# march_23_20_power_board1_v2_0.net
KiCad netlist of a schematic drawn in EAGLE
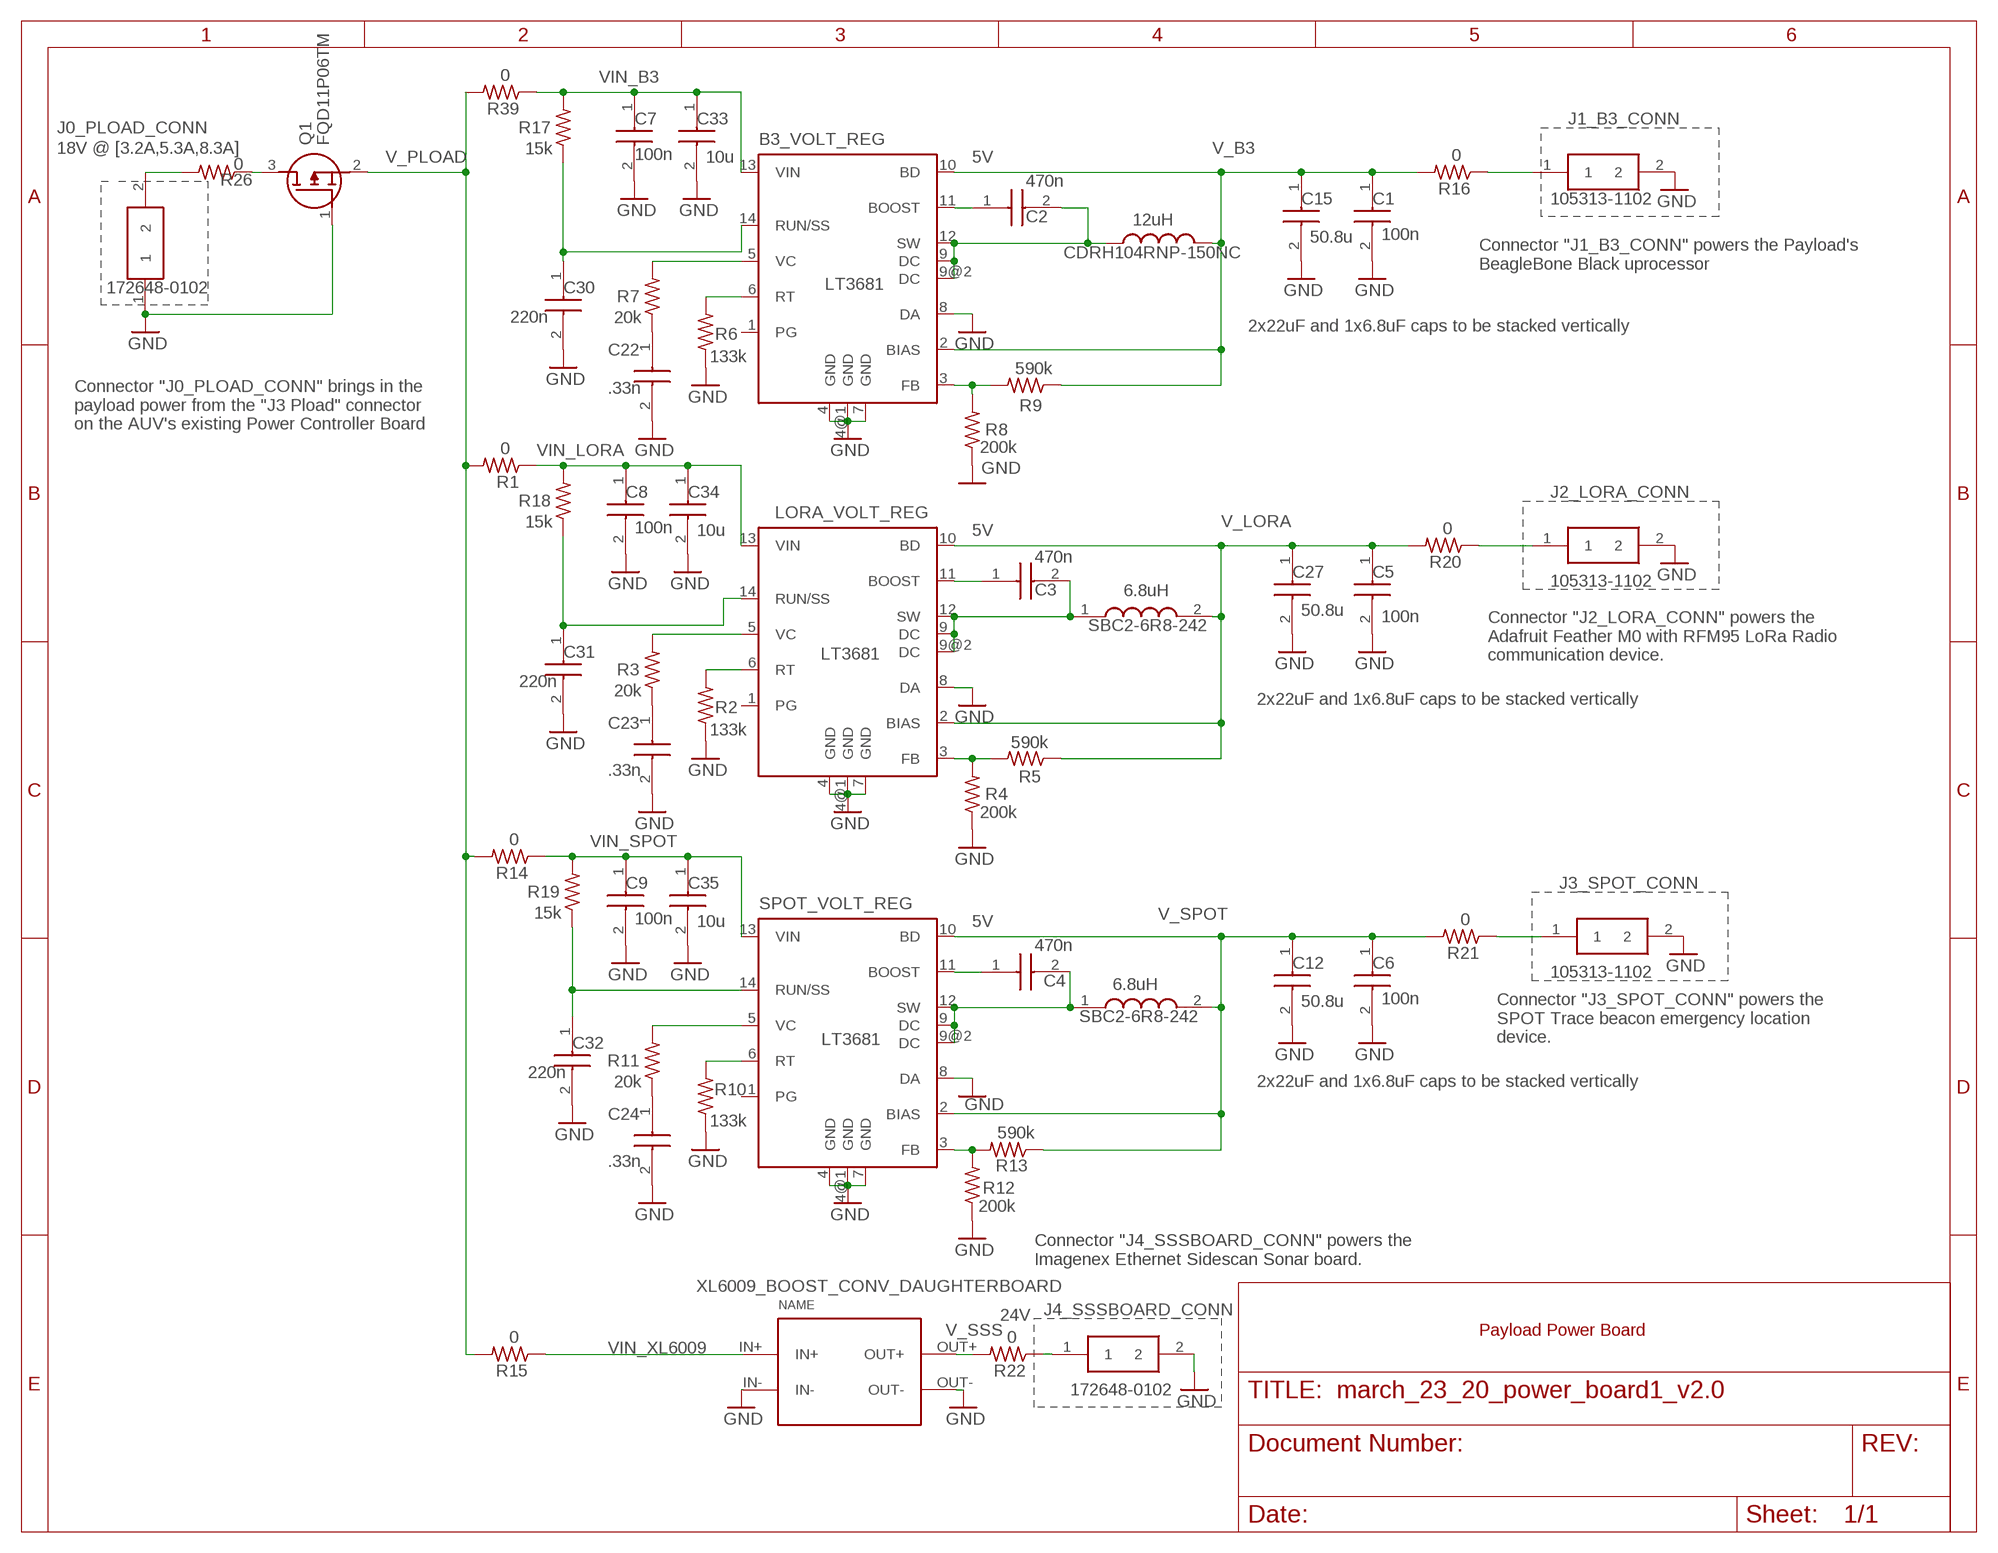
[diagram p0: schematic, sheet 1]

(export (version "E")
  (design (tool "Eeschema 10.0.6"))
  (components
    (comp (ref "B3_VOLT_REG")
      (value "LT3681")
      (footprint "eagle-import:DFN14-4X3DE")
      (fields (field (name "MPN") "LT3681EDE#PBF"))
      (libsource (lib "eagle-import") (part "LT3681"))
    )
    (comp (ref "C1")
      (value "100n")
      (footprint "eagle-import:CAPC1608X90N")
      (fields
        (field (name "MANUFACTURER_PART_NUMBER") "06033C104KAT4A")
        (field (name "MOUSER_PART_NUMBER") "581-06033C104KAT4A")
      )
      (libsource (lib "eagle-import") (part "06033C104KAT4A"))
    )
    (comp (ref "C2")
      (value "470n")
      (footprint "eagle-import:CAPC1608X90N")
      (fields
        (field (name "MANUFACTURER_PART_NUMBER") "06033C474JAT2A")
        (field (name "MOUSER_PART_NUMBER") "581-06033C474JAT2A")
      )
      (libsource (lib "eagle-import") (part "06033C474JAT2A"))
    )
    (comp (ref "C3")
      (value "470n")
      (footprint "eagle-import:CAPC1608X90N")
      (fields
        (field (name "MANUFACTURER_PART_NUMBER") "06033C474JAT2A")
        (field (name "MOUSER_PART_NUMBER") "581-06033C474JAT2A")
      )
      (libsource (lib "eagle-import") (part "06033C474JAT2A"))
    )
    (comp (ref "C4")
      (value "470n")
      (footprint "eagle-import:CAPC1608X90N")
      (fields
        (field (name "MANUFACTURER_PART_NUMBER") "06033C474JAT2A")
        (field (name "MOUSER_PART_NUMBER") "581-06033C474JAT2A")
      )
      (libsource (lib "eagle-import") (part "06033C474JAT2A"))
    )
    (comp (ref "C5")
      (value "100n")
      (footprint "eagle-import:CAPC1608X90N")
      (fields
        (field (name "MANUFACTURER_PART_NUMBER") "06033C104KAT4A")
        (field (name "MOUSER_PART_NUMBER") "581-06033C104KAT4A")
      )
      (libsource (lib "eagle-import") (part "06033C104KAT4A"))
    )
    (comp (ref "C6")
      (value "100n")
      (footprint "eagle-import:CAPC1608X90N")
      (fields
        (field (name "MANUFACTURER_PART_NUMBER") "06033C104KAT4A")
        (field (name "MOUSER_PART_NUMBER") "581-06033C104KAT4A")
      )
      (libsource (lib "eagle-import") (part "06033C104KAT4A"))
    )
    (comp (ref "C7")
      (value "100n")
      (footprint "eagle-import:CAPC1608X90N")
      (fields
        (field (name "MANUFACTURER_PART_NUMBER") "06031C104KAT2A")
        (field (name "MOUSER_PART_NUMBER") "581-06031C104KAT2A")
      )
      (libsource (lib "eagle-import") (part "06031C104KAT2A"))
    )
    (comp (ref "C8")
      (value "100n")
      (footprint "eagle-import:CAPC1608X90N")
      (fields
        (field (name "MANUFACTURER_PART_NUMBER") "06031C104KAT2A")
        (field (name "MOUSER_PART_NUMBER") "581-06031C104KAT2A")
      )
      (libsource (lib "eagle-import") (part "06031C104KAT2A"))
    )
    (comp (ref "C9")
      (value "100n")
      (footprint "eagle-import:CAPC1608X90N")
      (fields
        (field (name "MANUFACTURER_PART_NUMBER") "06031C104KAT2A")
        (field (name "MOUSER_PART_NUMBER") "581-06031C104KAT2A")
      )
      (libsource (lib "eagle-import") (part "06031C104KAT2A"))
    )
    (comp (ref "C12")
      (value "50.8u")
      (footprint "eagle-import:CAPC3225X279N")
      (fields
        (field (name "MANUFACTURER_PART_NUMBER") "12103C226KAT2A")
        (field (name "MOUSER_PART_NUMBER") "581-12103C226KAT2A")
      )
      (libsource (lib "eagle-import") (part "12103C226KAT2A"))
    )
    (comp (ref "C15")
      (value "50.8u")
      (footprint "eagle-import:CAPC3225X279N")
      (fields
        (field (name "MANUFACTURER_PART_NUMBER") "12103C226KAT2A")
        (field (name "MOUSER_PART_NUMBER") "581-12103C226KAT2A")
      )
      (libsource (lib "eagle-import") (part "12103C226KAT2A"))
    )
    (comp (ref "C22")
      (value ".33n")
      (footprint "eagle-import:CAPC2012X140N")
      (fields
        (field (name "MANUFACTURER_PART_NUMBER") "08053C334KAT2A")
        (field (name "MOUSER_PART_NUMBER") "581-08053C334KAT2A")
        (field (name "RS_PART_NUMBER") "1747387")
      )
      (libsource (lib "eagle-import") (part "08053C334KAT2A"))
    )
    (comp (ref "C23")
      (value ".33n")
      (footprint "eagle-import:CAPC2012X140N")
      (fields
        (field (name "MANUFACTURER_PART_NUMBER") "08053C334KAT2A")
        (field (name "MOUSER_PART_NUMBER") "581-08053C334KAT2A")
        (field (name "RS_PART_NUMBER") "1747387")
      )
      (libsource (lib "eagle-import") (part "08053C334KAT2A"))
    )
    (comp (ref "C24")
      (value ".33n")
      (footprint "eagle-import:CAPC2012X140N")
      (fields
        (field (name "MANUFACTURER_PART_NUMBER") "08053C334KAT2A")
        (field (name "MOUSER_PART_NUMBER") "581-08053C334KAT2A")
        (field (name "RS_PART_NUMBER") "1747387")
      )
      (libsource (lib "eagle-import") (part "08053C334KAT2A"))
    )
    (comp (ref "C27")
      (value "50.8u")
      (footprint "eagle-import:CAPC3225X279N")
      (fields
        (field (name "MANUFACTURER_PART_NUMBER") "12103C226KAT2A")
        (field (name "MOUSER_PART_NUMBER") "581-12103C226KAT2A")
      )
      (libsource (lib "eagle-import") (part "12103C226KAT2A"))
    )
    (comp (ref "C30")
      (value "220n")
      (footprint "eagle-import:CAPC2012X140N")
      (fields
        (field (name "MANUFACTURER_PART_NUMBER") "08051C224KAT2A")
        (field (name "MOUSER_PART_NUMBER") "581-08051C224KAT2A")
      )
      (libsource (lib "eagle-import") (part "08051C224KAT2A"))
    )
    (comp (ref "C31")
      (value "220n")
      (footprint "eagle-import:CAPC2012X140N")
      (fields
        (field (name "MANUFACTURER_PART_NUMBER") "08051C224KAT2A")
        (field (name "MOUSER_PART_NUMBER") "581-08051C224KAT2A")
      )
      (libsource (lib "eagle-import") (part "08051C224KAT2A"))
    )
    (comp (ref "C32")
      (value "220n")
      (footprint "eagle-import:CAPC2012X140N")
      (fields
        (field (name "MANUFACTURER_PART_NUMBER") "08051C224KAT2A")
        (field (name "MOUSER_PART_NUMBER") "581-08051C224KAT2A")
      )
      (libsource (lib "eagle-import") (part "08051C224KAT2A"))
    )
    (comp (ref "C33")
      (value "10u")
      (footprint "eagle-import:CAPC5750X279N")
      (fields
        (field (name "MANUFACTURER_PART_NUMBER") "22201C106KAT2A")
        (field (name "MOUSER_PART_NUMBER") "581-22201C106KAT2A")
      )
      (libsource (lib "eagle-import") (part "22201C106KAT2A"))
    )
    (comp (ref "C34")
      (value "10u")
      (footprint "eagle-import:CAPC5750X279N")
      (fields
        (field (name "MANUFACTURER_PART_NUMBER") "22201C106KAT2A")
        (field (name "MOUSER_PART_NUMBER") "581-22201C106KAT2A")
      )
      (libsource (lib "eagle-import") (part "22201C106KAT2A"))
    )
    (comp (ref "C35")
      (value "10u")
      (footprint "eagle-import:CAPC5750X279N")
      (fields
        (field (name "MANUFACTURER_PART_NUMBER") "22201C106KAT2A")
        (field (name "MOUSER_PART_NUMBER") "581-22201C106KAT2A")
      )
      (libsource (lib "eagle-import") (part "22201C106KAT2A"))
    )
    (comp (ref "INDUCTOR_3")
      (value "CDRH104RNP-150NC")
      (footprint "eagle-import:INDPM102100X400N")
      (fields (field (name "MOUSER_PART_NUMBER") "851-CDRH104RNP-150NC"))
      (libsource (lib "eagle-import") (part "CDRH104RNP-150NC"))
    )
    (comp (ref "J0_PLOAD_CONN")
      (value "172648-0102")
      (footprint "eagle-import:1726480102")
      (fields (field (name "MOUSER_PART_NUMBER") "538-172648-0102"))
      (libsource (lib "eagle-import") (part "172648-0102"))
    )
    (comp (ref "J1_B3_CONN")
      (value "105313-1102")
      (footprint "eagle-import:1053131102")
      (fields (field (name "MOUSER_PART_NUMBER") "538-105313-1102") (field (name "RS_PART_NUMBER") "1623686"))
      (libsource (lib "eagle-import") (part "105313-1102"))
    )
    (comp (ref "J2_LORA_CONN")
      (value "105313-1102")
      (footprint "eagle-import:1053131102")
      (fields (field (name "MOUSER_PART_NUMBER") "538-105313-1102") (field (name "RS_PART_NUMBER") "1623686"))
      (libsource (lib "eagle-import") (part "105313-1102"))
    )
    (comp (ref "J3_SPOT_CONN")
      (value "105313-1102")
      (footprint "eagle-import:1053131102")
      (fields (field (name "MOUSER_PART_NUMBER") "538-105313-1102") (field (name "RS_PART_NUMBER") "1623686"))
      (libsource (lib "eagle-import") (part "105313-1102"))
    )
    (comp (ref "J4_SSSBOARD_CONN")
      (value "172648-0102")
      (footprint "eagle-import:1726480102")
      (fields (field (name "MOUSER_PART_NUMBER") "538-172648-0102"))
      (libsource (lib "eagle-import") (part "172648-0102"))
    )
    (comp (ref "L4")
      (value "SBC2-6R8-242")
      (footprint "eagle-import:SBC26R8242")
      (fields (field (name "MOUSER_PART_NUMBER") "80-SBC2-6R8-242"))
      (libsource (lib "eagle-import") (part "SBC2-6R8-242"))
    )
    (comp (ref "L5")
      (value "SBC2-6R8-242")
      (footprint "eagle-import:SBC26R8242")
      (fields (field (name "MOUSER_PART_NUMBER") "80-SBC2-6R8-242"))
      (libsource (lib "eagle-import") (part "SBC2-6R8-242"))
    )
    (comp (ref "LORA_VOLT_REG")
      (value "LT3681")
      (footprint "eagle-import:DFN14-4X3DE")
      (fields (field (name "MPN") "LT3681EDE#PBF"))
      (libsource (lib "eagle-import") (part "LT3681"))
    )
    (comp (ref "Q1")
      (value "FQD11P06TM")
      (footprint "eagle-import:DPAK3-CASE-369AS")
      (fields (field (name "MOUSER_PART_NUMBER") "512-FQD11P06TM") (field (name "RS_PART_NUMBER") "6710949P"))
      (libsource (lib "eagle-import") (part "FQD11P06TM"))
    )
    (comp (ref "R1")
      (value "0")
      (footprint "eagle-import:0207_2V")
      (fields (field (name "MFR") "Yageo") (field (name "MPN") "RC0805FR-0710KL"))
      (libsource (lib "eagle-import") (part "R-US_0207/2V"))
    )
    (comp (ref "R2")
      (value "133k")
      (footprint "eagle-import:R0603")
      (libsource (lib "eagle-import") (part "R-US_R0603"))
    )
    (comp (ref "R3")
      (value "20k")
      (footprint "eagle-import:R0603")
      (libsource (lib "eagle-import") (part "R-US_R0603"))
    )
    (comp (ref "R4")
      (value "200k")
      (footprint "eagle-import:R0603")
      (libsource (lib "eagle-import") (part "R-US_R0603"))
    )
    (comp (ref "R5")
      (value "590k")
      (footprint "eagle-import:R0603")
      (libsource (lib "eagle-import") (part "R-US_R0603"))
    )
    (comp (ref "R6")
      (value "133k")
      (footprint "eagle-import:R0603")
      (libsource (lib "eagle-import") (part "R-US_R0603"))
    )
    (comp (ref "R7")
      (value "20k")
      (footprint "eagle-import:R0603")
      (libsource (lib "eagle-import") (part "R-US_R0603"))
    )
    (comp (ref "R8")
      (value "200k")
      (footprint "eagle-import:R0603")
      (libsource (lib "eagle-import") (part "R-US_R0603"))
    )
    (comp (ref "R9")
      (value "590k")
      (footprint "eagle-import:R0603")
      (libsource (lib "eagle-import") (part "R-US_R0603"))
    )
    (comp (ref "R10")
      (value "133k")
      (footprint "eagle-import:R0603")
      (libsource (lib "eagle-import") (part "R-US_R0603"))
    )
    (comp (ref "R11")
      (value "20k")
      (footprint "eagle-import:R0603")
      (libsource (lib "eagle-import") (part "R-US_R0603"))
    )
    (comp (ref "R12")
      (value "200k")
      (footprint "eagle-import:R0603")
      (libsource (lib "eagle-import") (part "R-US_R0603"))
    )
    (comp (ref "R13")
      (value "590k")
      (footprint "eagle-import:R0603")
      (libsource (lib "eagle-import") (part "R-US_R0603"))
    )
    (comp (ref "R14")
      (value "0")
      (footprint "eagle-import:0207_2V")
      (fields (field (name "MFR") "Yageo") (field (name "MPN") "RC0805FR-0710KL"))
      (libsource (lib "eagle-import") (part "R-US_0207/2V"))
    )
    (comp (ref "R15")
      (value "0")
      (footprint "eagle-import:0207_2V")
      (fields (field (name "MFR") "Yageo") (field (name "MPN") "RC0805FR-0710KL"))
      (libsource (lib "eagle-import") (part "R-US_0207/2V"))
    )
    (comp (ref "R16")
      (value "0")
      (footprint "eagle-import:0207_2V")
      (fields (field (name "MFR") "Yageo") (field (name "MPN") "RC0805FR-0710KL"))
      (libsource (lib "eagle-import") (part "R-US_0207/2V"))
    )
    (comp (ref "R17")
      (value "15k")
      (footprint "eagle-import:R0603")
      (libsource (lib "eagle-import") (part "R-US_R0603"))
    )
    (comp (ref "R18")
      (value "15k")
      (footprint "eagle-import:R0603")
      (libsource (lib "eagle-import") (part "R-US_R0603"))
    )
    (comp (ref "R19")
      (value "15k")
      (footprint "eagle-import:R0603")
      (libsource (lib "eagle-import") (part "R-US_R0603"))
    )
    (comp (ref "R20")
      (value "0")
      (footprint "eagle-import:0207_2V")
      (fields (field (name "MFR") "Yageo") (field (name "MPN") "RC0805FR-0710KL"))
      (libsource (lib "eagle-import") (part "R-US_0207/2V"))
    )
    (comp (ref "R21")
      (value "0")
      (footprint "eagle-import:0207_2V")
      (fields (field (name "MFR") "Yageo") (field (name "MPN") "RC0805FR-0710KL"))
      (libsource (lib "eagle-import") (part "R-US_0207/2V"))
    )
    (comp (ref "R22")
      (value "0")
      (footprint "eagle-import:0207_2V")
      (fields (field (name "MFR") "Yageo") (field (name "MPN") "RC0805FR-0710KL"))
      (libsource (lib "eagle-import") (part "R-US_0207/2V"))
    )
    (comp (ref "R26")
      (value "0")
      (footprint "eagle-import:0207_2V")
      (fields (field (name "MFR") "Yageo") (field (name "MPN") "RC0805FR-0710KL"))
      (libsource (lib "eagle-import") (part "R-US_0207/2V"))
    )
    (comp (ref "R39")
      (value "0")
      (footprint "eagle-import:0207_2V")
      (fields (field (name "MFR") "Yageo") (field (name "MPN") "RC0805FR-0710KL"))
      (libsource (lib "eagle-import") (part "R-US_0207/2V"))
    )
    (comp (ref "SPOT_VOLT_REG")
      (value "LT3681")
      (footprint "eagle-import:DFN14-4X3DE")
      (fields (field (name "MPN") "LT3681EDE#PBF"))
      (libsource (lib "eagle-import") (part "LT3681"))
    )
    (comp (ref "XL6009_BOOST_CONV_DAUGHTERBOARD")
      (value "CP8-ADJ")
      (footprint "eagle-import:CP8-ADJ")
      (libsource (lib "eagle-import") (part "CP8-ADJ"))
    )
  )
  (nets
    (net (code "1") (name "/VIN_B3") (class "Default")
      (node (ref "B3_VOLT_REG") (pin "13") (pinfunction "VIN_13") (pintype "input"))
      (node (ref "C33") (pin "1") (pinfunction "1_1") (pintype "bidirectional"))
      (node (ref "C7") (pin "1") (pinfunction "1_1") (pintype "bidirectional"))
      (node (ref "R17") (pin "2") (pinfunction "2_2") (pintype "passive"))
      (node (ref "R39") (pin "1") (pinfunction "1_1") (pintype "passive"))
    )
    (net (code "2") (name "/VIN_LORA") (class "Default")
      (node (ref "C34") (pin "1") (pinfunction "1_1") (pintype "bidirectional"))
      (node (ref "C8") (pin "1") (pinfunction "1_1") (pintype "bidirectional"))
      (node (ref "LORA_VOLT_REG") (pin "13") (pinfunction "VIN_13") (pintype "input"))
      (node (ref "R1") (pin "1") (pinfunction "1_1") (pintype "passive"))
      (node (ref "R18") (pin "2") (pinfunction "2_2") (pintype "passive"))
    )
    (net (code "3") (name "/VIN_SPOT") (class "Default")
      (node (ref "C35") (pin "1") (pinfunction "1_1") (pintype "bidirectional"))
      (node (ref "C9") (pin "1") (pinfunction "1_1") (pintype "bidirectional"))
      (node (ref "R14") (pin "1") (pinfunction "1_1") (pintype "passive"))
      (node (ref "R19") (pin "2") (pinfunction "2_2") (pintype "passive"))
      (node (ref "SPOT_VOLT_REG") (pin "13") (pinfunction "VIN_13") (pintype "input"))
    )
    (net (code "4") (name "/VIN_XL6009") (class "Default")
      (node (ref "R15") (pin "1") (pinfunction "1_1") (pintype "passive"))
      (node (ref "XL6009_BOOST_CONV_DAUGHTERBOARD") (pin "IN+") (pinfunction "IN+_IN+") (pintype "passive"))
    )
    (net (code "5") (name "/V_B3") (class "Default")
      (node (ref "B3_VOLT_REG") (pin "10") (pinfunction "BD_10") (pintype "input"))
      (node (ref "B3_VOLT_REG") (pin "2") (pinfunction "BIAS_2") (pintype "input"))
      (node (ref "C1") (pin "1") (pinfunction "1_1") (pintype "bidirectional"))
      (node (ref "C15") (pin "1") (pinfunction "1_1") (pintype "bidirectional"))
      (node (ref "INDUCTOR_3") (pin "2") (pinfunction "2_2") (pintype "passive"))
      (node (ref "R16") (pin "2") (pinfunction "2_2") (pintype "passive"))
      (node (ref "R9") (pin "1") (pinfunction "1_1") (pintype "passive"))
    )
    (net (code "6") (name "/V_LORA") (class "Default")
      (node (ref "C27") (pin "1") (pinfunction "1_1") (pintype "bidirectional"))
      (node (ref "C5") (pin "1") (pinfunction "1_1") (pintype "bidirectional"))
      (node (ref "L5") (pin "2") (pinfunction "2_2") (pintype "bidirectional"))
      (node (ref "LORA_VOLT_REG") (pin "10") (pinfunction "BD_10") (pintype "input"))
      (node (ref "LORA_VOLT_REG") (pin "2") (pinfunction "BIAS_2") (pintype "input"))
      (node (ref "R20") (pin "2") (pinfunction "2_2") (pintype "passive"))
      (node (ref "R5") (pin "1") (pinfunction "1_1") (pintype "passive"))
    )
    (net (code "7") (name "/V_PLOAD") (class "Default")
      (node (ref "Q1") (pin "2") (pinfunction "S_2") (pintype "bidirectional"))
      (node (ref "R1") (pin "2") (pinfunction "2_2") (pintype "passive"))
      (node (ref "R14") (pin "2") (pinfunction "2_2") (pintype "passive"))
      (node (ref "R15") (pin "2") (pinfunction "2_2") (pintype "passive"))
      (node (ref "R39") (pin "2") (pinfunction "2_2") (pintype "passive"))
    )
    (net (code "8") (name "/V_SPOT") (class "Default")
      (node (ref "C12") (pin "1") (pinfunction "1_1") (pintype "bidirectional"))
      (node (ref "C6") (pin "1") (pinfunction "1_1") (pintype "bidirectional"))
      (node (ref "L4") (pin "2") (pinfunction "2_2") (pintype "bidirectional"))
      (node (ref "R13") (pin "1") (pinfunction "1_1") (pintype "passive"))
      (node (ref "R21") (pin "2") (pinfunction "2_2") (pintype "passive"))
      (node (ref "SPOT_VOLT_REG") (pin "10") (pinfunction "BD_10") (pintype "input"))
      (node (ref "SPOT_VOLT_REG") (pin "2") (pinfunction "BIAS_2") (pintype "input"))
    )
    (net (code "9") (name "/V_SSS") (class "Default")
      (node (ref "R22") (pin "2") (pinfunction "2_2") (pintype "passive"))
      (node (ref "XL6009_BOOST_CONV_DAUGHTERBOARD") (pin "OUT+") (pinfunction "OUT+_OUT+") (pintype "passive"))
    )
    (net (code "10") (name "GND") (class "Default")
      (node (ref "B3_VOLT_REG") (pin "4") (pinfunction "GND_4") (pintype "input"))
      (node (ref "B3_VOLT_REG") (pin "4@1") (pinfunction "GND_4@1") (pintype "input"))
      (node (ref "B3_VOLT_REG") (pin "7") (pinfunction "GND_7") (pintype "input"))
      (node (ref "B3_VOLT_REG") (pin "8") (pinfunction "DA_8") (pintype "passive"))
      (node (ref "C1") (pin "2") (pinfunction "2_2") (pintype "bidirectional"))
      (node (ref "C12") (pin "2") (pinfunction "2_2") (pintype "bidirectional"))
      (node (ref "C15") (pin "2") (pinfunction "2_2") (pintype "bidirectional"))
      (node (ref "C22") (pin "2") (pinfunction "2_2") (pintype "bidirectional"))
      (node (ref "C23") (pin "2") (pinfunction "2_2") (pintype "bidirectional"))
      (node (ref "C24") (pin "2") (pinfunction "2_2") (pintype "bidirectional"))
      (node (ref "C27") (pin "2") (pinfunction "2_2") (pintype "bidirectional"))
      (node (ref "C30") (pin "2") (pinfunction "2_2") (pintype "bidirectional"))
      (node (ref "C31") (pin "2") (pinfunction "2_2") (pintype "bidirectional"))
      (node (ref "C32") (pin "2") (pinfunction "2_2") (pintype "bidirectional"))
      (node (ref "C33") (pin "2") (pinfunction "2_2") (pintype "bidirectional"))
      (node (ref "C34") (pin "2") (pinfunction "2_2") (pintype "bidirectional"))
      (node (ref "C35") (pin "2") (pinfunction "2_2") (pintype "bidirectional"))
      (node (ref "C5") (pin "2") (pinfunction "2_2") (pintype "bidirectional"))
      (node (ref "C6") (pin "2") (pinfunction "2_2") (pintype "bidirectional"))
      (node (ref "C7") (pin "2") (pinfunction "2_2") (pintype "bidirectional"))
      (node (ref "C8") (pin "2") (pinfunction "2_2") (pintype "bidirectional"))
      (node (ref "C9") (pin "2") (pinfunction "2_2") (pintype "bidirectional"))
      (node (ref "J0_PLOAD_CONN") (pin "1") (pinfunction "1_1") (pintype "bidirectional"))
      (node (ref "J1_B3_CONN") (pin "2") (pinfunction "2_2") (pintype "bidirectional"))
      (node (ref "J2_LORA_CONN") (pin "2") (pinfunction "2_2") (pintype "bidirectional"))
      (node (ref "J3_SPOT_CONN") (pin "2") (pinfunction "2_2") (pintype "bidirectional"))
      (node (ref "J4_SSSBOARD_CONN") (pin "2") (pinfunction "2_2") (pintype "bidirectional"))
      (node (ref "LORA_VOLT_REG") (pin "4") (pinfunction "GND_4") (pintype "input"))
      (node (ref "LORA_VOLT_REG") (pin "4@1") (pinfunction "GND_4@1") (pintype "input"))
      (node (ref "LORA_VOLT_REG") (pin "7") (pinfunction "GND_7") (pintype "input"))
      (node (ref "LORA_VOLT_REG") (pin "8") (pinfunction "DA_8") (pintype "passive"))
      (node (ref "Q1") (pin "1") (pinfunction "G_1") (pintype "bidirectional"))
      (node (ref "R10") (pin "1") (pinfunction "1_1") (pintype "passive"))
      (node (ref "R12") (pin "1") (pinfunction "1_1") (pintype "passive"))
      (node (ref "R2") (pin "1") (pinfunction "1_1") (pintype "passive"))
      (node (ref "R4") (pin "1") (pinfunction "1_1") (pintype "passive"))
      (node (ref "R6") (pin "1") (pinfunction "1_1") (pintype "passive"))
      (node (ref "R8") (pin "1") (pinfunction "1_1") (pintype "passive"))
      (node (ref "SPOT_VOLT_REG") (pin "4") (pinfunction "GND_4") (pintype "input"))
      (node (ref "SPOT_VOLT_REG") (pin "4@1") (pinfunction "GND_4@1") (pintype "input"))
      (node (ref "SPOT_VOLT_REG") (pin "7") (pinfunction "GND_7") (pintype "input"))
      (node (ref "SPOT_VOLT_REG") (pin "8") (pinfunction "DA_8") (pintype "passive"))
      (node (ref "XL6009_BOOST_CONV_DAUGHTERBOARD") (pin "IN-") (pinfunction "IN-_IN-") (pintype "passive"))
      (node (ref "XL6009_BOOST_CONV_DAUGHTERBOARD") (pin "OUT-") (pinfunction "OUT-_OUT-") (pintype "passive"))
    )
    (net (code "11") (name "Net-(B3_VOLT_REG-BOOST)") (class "Default")
      (node (ref "B3_VOLT_REG") (pin "11") (pinfunction "BOOST_11") (pintype "output"))
      (node (ref "C2") (pin "1") (pinfunction "1_1") (pintype "bidirectional"))
    )
    (net (code "12") (name "Net-(B3_VOLT_REG-FB)") (class "Default")
      (node (ref "B3_VOLT_REG") (pin "3") (pinfunction "FB_3") (pintype "input"))
      (node (ref "R8") (pin "2") (pinfunction "2_2") (pintype "passive"))
      (node (ref "R9") (pin "2") (pinfunction "2_2") (pintype "passive"))
    )
    (net (code "13") (name "Net-(B3_VOLT_REG-RT)") (class "Default")
      (node (ref "B3_VOLT_REG") (pin "6") (pinfunction "RT_6") (pintype "input"))
      (node (ref "R6") (pin "2") (pinfunction "2_2") (pintype "passive"))
    )
    (net (code "14") (name "Net-(B3_VOLT_REG-RUN{slash}SS)") (class "Default")
      (node (ref "B3_VOLT_REG") (pin "14") (pinfunction "RUN/SS_14") (pintype "input"))
      (node (ref "C30") (pin "1") (pinfunction "1_1") (pintype "bidirectional"))
      (node (ref "R17") (pin "1") (pinfunction "1_1") (pintype "passive"))
    )
    (net (code "15") (name "Net-(B3_VOLT_REG-SW)") (class "Default")
      (node (ref "B3_VOLT_REG") (pin "12") (pinfunction "SW_12") (pintype "output"))
      (node (ref "B3_VOLT_REG") (pin "9") (pinfunction "DC_9") (pintype "passive"))
      (node (ref "B3_VOLT_REG") (pin "9@2") (pinfunction "DC_9@2") (pintype "passive"))
      (node (ref "C2") (pin "2") (pinfunction "2_2") (pintype "bidirectional"))
      (node (ref "INDUCTOR_3") (pin "1") (pinfunction "1_1") (pintype "passive"))
    )
    (net (code "16") (name "Net-(B3_VOLT_REG-VC)") (class "Default")
      (node (ref "B3_VOLT_REG") (pin "5") (pinfunction "VC_5") (pintype "output"))
      (node (ref "R7") (pin "2") (pinfunction "2_2") (pintype "passive"))
    )
    (net (code "17") (name "Net-(C22-Pad1)") (class "Default")
      (node (ref "C22") (pin "1") (pinfunction "1_1") (pintype "bidirectional"))
      (node (ref "R7") (pin "1") (pinfunction "1_1") (pintype "passive"))
    )
    (net (code "18") (name "Net-(C23-Pad1)") (class "Default")
      (node (ref "C23") (pin "1") (pinfunction "1_1") (pintype "bidirectional"))
      (node (ref "R3") (pin "1") (pinfunction "1_1") (pintype "passive"))
    )
    (net (code "19") (name "Net-(C24-Pad1)") (class "Default")
      (node (ref "C24") (pin "1") (pinfunction "1_1") (pintype "bidirectional"))
      (node (ref "R11") (pin "1") (pinfunction "1_1") (pintype "passive"))
    )
    (net (code "20") (name "Net-(J0_PLOAD_CONN-Pad2)") (class "Default")
      (node (ref "J0_PLOAD_CONN") (pin "2") (pinfunction "2_2") (pintype "bidirectional"))
      (node (ref "R26") (pin "2") (pinfunction "2_2") (pintype "passive"))
    )
    (net (code "21") (name "Net-(J1_B3_CONN-Pad1)") (class "Default")
      (node (ref "J1_B3_CONN") (pin "1") (pinfunction "1_1") (pintype "bidirectional"))
      (node (ref "R16") (pin "1") (pinfunction "1_1") (pintype "passive"))
    )
    (net (code "22") (name "Net-(J2_LORA_CONN-Pad1)") (class "Default")
      (node (ref "J2_LORA_CONN") (pin "1") (pinfunction "1_1") (pintype "bidirectional"))
      (node (ref "R20") (pin "1") (pinfunction "1_1") (pintype "passive"))
    )
    (net (code "23") (name "Net-(J3_SPOT_CONN-Pad1)") (class "Default")
      (node (ref "J3_SPOT_CONN") (pin "1") (pinfunction "1_1") (pintype "bidirectional"))
      (node (ref "R21") (pin "1") (pinfunction "1_1") (pintype "passive"))
    )
    (net (code "24") (name "Net-(J4_SSSBOARD_CONN-Pad1)") (class "Default")
      (node (ref "J4_SSSBOARD_CONN") (pin "1") (pinfunction "1_1") (pintype "bidirectional"))
      (node (ref "R22") (pin "1") (pinfunction "1_1") (pintype "passive"))
    )
    (net (code "25") (name "Net-(LORA_VOLT_REG-BOOST)") (class "Default")
      (node (ref "C3") (pin "1") (pinfunction "1_1") (pintype "bidirectional"))
      (node (ref "LORA_VOLT_REG") (pin "11") (pinfunction "BOOST_11") (pintype "output"))
    )
    (net (code "26") (name "Net-(LORA_VOLT_REG-FB)") (class "Default")
      (node (ref "LORA_VOLT_REG") (pin "3") (pinfunction "FB_3") (pintype "input"))
      (node (ref "R4") (pin "2") (pinfunction "2_2") (pintype "passive"))
      (node (ref "R5") (pin "2") (pinfunction "2_2") (pintype "passive"))
    )
    (net (code "27") (name "Net-(LORA_VOLT_REG-RT)") (class "Default")
      (node (ref "LORA_VOLT_REG") (pin "6") (pinfunction "RT_6") (pintype "input"))
      (node (ref "R2") (pin "2") (pinfunction "2_2") (pintype "passive"))
    )
    (net (code "28") (name "Net-(LORA_VOLT_REG-RUN{slash}SS)") (class "Default")
      (node (ref "C31") (pin "1") (pinfunction "1_1") (pintype "bidirectional"))
      (node (ref "LORA_VOLT_REG") (pin "14") (pinfunction "RUN/SS_14") (pintype "input"))
      (node (ref "R18") (pin "1") (pinfunction "1_1") (pintype "passive"))
    )
    (net (code "29") (name "Net-(LORA_VOLT_REG-SW)") (class "Default")
      (node (ref "C3") (pin "2") (pinfunction "2_2") (pintype "bidirectional"))
      (node (ref "L5") (pin "1") (pinfunction "1_1") (pintype "bidirectional"))
      (node (ref "LORA_VOLT_REG") (pin "12") (pinfunction "SW_12") (pintype "output"))
      (node (ref "LORA_VOLT_REG") (pin "9") (pinfunction "DC_9") (pintype "passive"))
      (node (ref "LORA_VOLT_REG") (pin "9@2") (pinfunction "DC_9@2") (pintype "passive"))
    )
    (net (code "30") (name "Net-(LORA_VOLT_REG-VC)") (class "Default")
      (node (ref "LORA_VOLT_REG") (pin "5") (pinfunction "VC_5") (pintype "output"))
      (node (ref "R3") (pin "2") (pinfunction "2_2") (pintype "passive"))
    )
    (net (code "31") (name "Net-(Q1-D)") (class "Default")
      (node (ref "Q1") (pin "3") (pinfunction "D_3") (pintype "bidirectional"))
      (node (ref "R26") (pin "1") (pinfunction "1_1") (pintype "passive"))
    )
    (net (code "32") (name "Net-(SPOT_VOLT_REG-BOOST)") (class "Default")
      (node (ref "C4") (pin "1") (pinfunction "1_1") (pintype "bidirectional"))
      (node (ref "SPOT_VOLT_REG") (pin "11") (pinfunction "BOOST_11") (pintype "output"))
    )
    (net (code "33") (name "Net-(SPOT_VOLT_REG-FB)") (class "Default")
      (node (ref "R12") (pin "2") (pinfunction "2_2") (pintype "passive"))
      (node (ref "R13") (pin "2") (pinfunction "2_2") (pintype "passive"))
      (node (ref "SPOT_VOLT_REG") (pin "3") (pinfunction "FB_3") (pintype "input"))
    )
    (net (code "34") (name "Net-(SPOT_VOLT_REG-RT)") (class "Default")
      (node (ref "R10") (pin "2") (pinfunction "2_2") (pintype "passive"))
      (node (ref "SPOT_VOLT_REG") (pin "6") (pinfunction "RT_6") (pintype "input"))
    )
    (net (code "35") (name "Net-(SPOT_VOLT_REG-RUN{slash}SS)") (class "Default")
      (node (ref "C32") (pin "1") (pinfunction "1_1") (pintype "bidirectional"))
      (node (ref "R19") (pin "1") (pinfunction "1_1") (pintype "passive"))
      (node (ref "SPOT_VOLT_REG") (pin "14") (pinfunction "RUN/SS_14") (pintype "input"))
    )
    (net (code "36") (name "Net-(SPOT_VOLT_REG-SW)") (class "Default")
      (node (ref "C4") (pin "2") (pinfunction "2_2") (pintype "bidirectional"))
      (node (ref "L4") (pin "1") (pinfunction "1_1") (pintype "bidirectional"))
      (node (ref "SPOT_VOLT_REG") (pin "12") (pinfunction "SW_12") (pintype "output"))
      (node (ref "SPOT_VOLT_REG") (pin "9") (pinfunction "DC_9") (pintype "passive"))
      (node (ref "SPOT_VOLT_REG") (pin "9@2") (pinfunction "DC_9@2") (pintype "passive"))
    )
    (net (code "37") (name "Net-(SPOT_VOLT_REG-VC)") (class "Default")
      (node (ref "R11") (pin "2") (pinfunction "2_2") (pintype "passive"))
      (node (ref "SPOT_VOLT_REG") (pin "5") (pinfunction "VC_5") (pintype "output"))
    )
    (net (code "38") (name "unconnected-(B3_VOLT_REG-PG-Pad1)") (class "Default")
      (node (ref "B3_VOLT_REG") (pin "1") (pinfunction "PG_1") (pintype "open_collector"))
    )
    (net (code "39") (name "unconnected-(LORA_VOLT_REG-PG-Pad1)") (class "Default")
      (node (ref "LORA_VOLT_REG") (pin "1") (pinfunction "PG_1") (pintype "open_collector"))
    )
    (net (code "40") (name "unconnected-(SPOT_VOLT_REG-PG-Pad1)") (class "Default")
      (node (ref "SPOT_VOLT_REG") (pin "1") (pinfunction "PG_1") (pintype "open_collector"))
    )
  )
)
